# relay_board.net
KiCad netlist of a schematic drawn in EAGLE
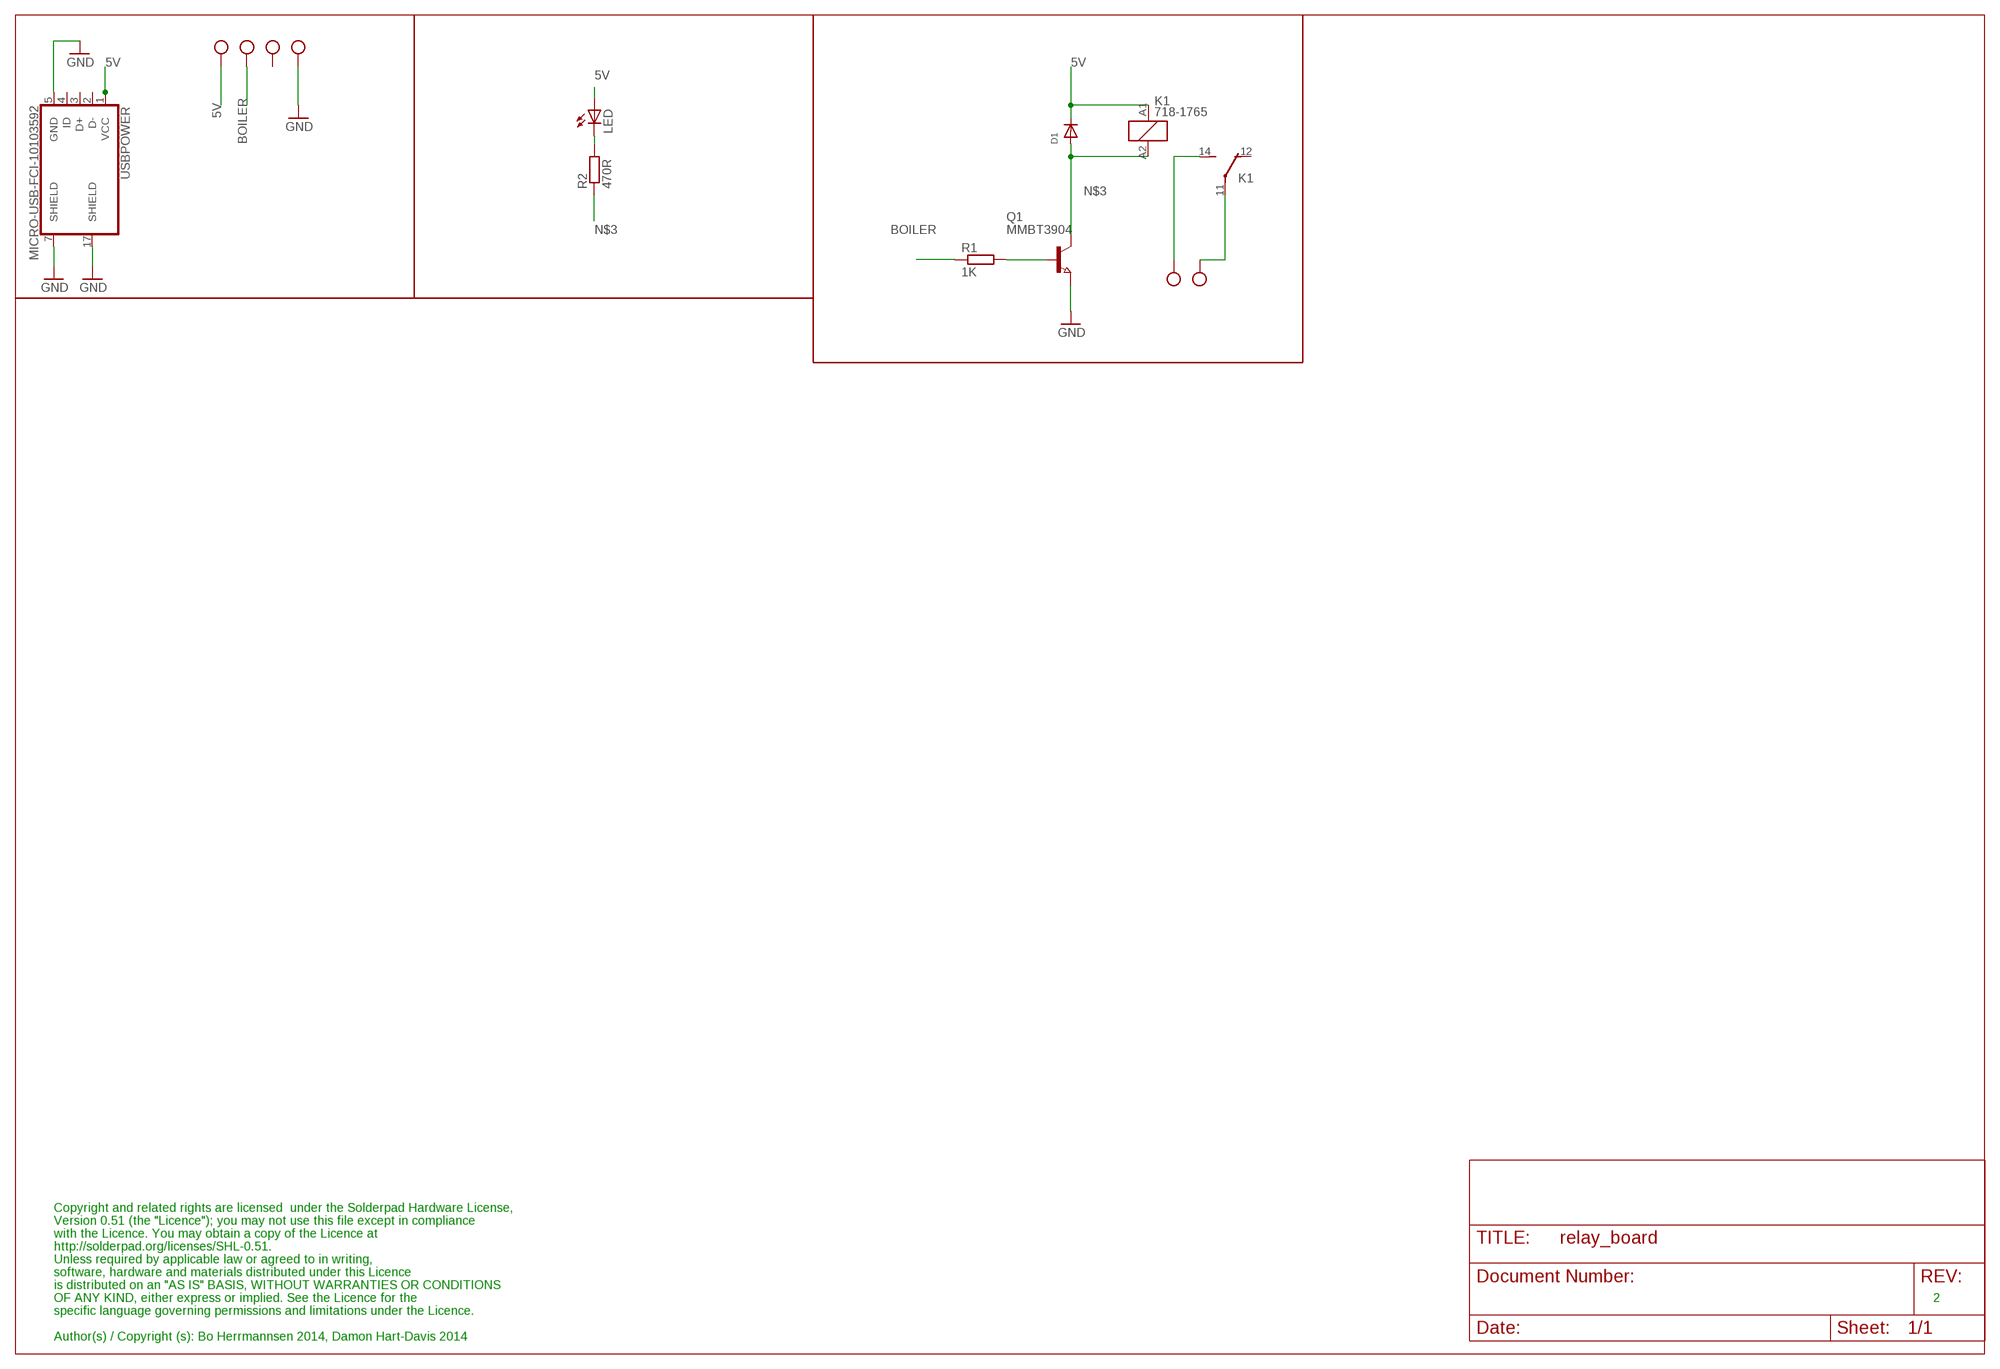
[diagram p0: schematic, sheet 1]

(export (version "E")
  (design (tool "Eeschema 10.0.6"))
  (components
    (comp (ref "D1")
      (value "DIODESMA")
      (footprint "eagle-import:SMADIODE")
      (libsource (lib "eagle-import") (part "DIODESMA"))
    )
    (comp (ref "K1")
      (value "718-1765")
      (footprint "eagle-import:718-1765")
      (libsource (lib "eagle-import") (part "718-1765"))
    )
    (comp (ref "LED")
      (value "LED3MM")
      (footprint "eagle-import:LED3MM")
      (libsource (lib "eagle-import") (part "LED3MM"))
    )
    (comp (ref "Q1")
      (value "MMBT3904")
      (footprint "eagle-import:SOT23")
      (libsource (lib "eagle-import") (part "NPN-TRANSISTOR_SOT23"))
    )
    (comp (ref "R1")
      (value "1K")
      (footprint "eagle-import:R0603")
      (libsource (lib "eagle-import") (part "R-EU_R0603"))
    )
    (comp (ref "R2")
      (value "470R")
      (footprint "eagle-import:R0603")
      (libsource (lib "eagle-import") (part "R-EU_R0603"))
    )
    (comp (ref "USBPOWER")
      (value "MICRO-USB-FCI-10103592")
      (footprint "eagle-import:MICRO-USB-FCI-10103592")
      (libsource (lib "eagle-import") (part "MICRO-USB-FCI-10103592"))
    )
    (comp (ref "X1")
      (value "W237-102")
      (footprint "eagle-import:SCREWTERMINAL")
      (fields (field (name "MPN") "237-102"))
      (libsource (lib "eagle-import") (part "W237-102"))
    )
    (comp (ref "X2")
      (value "W237-102")
      (footprint "eagle-import:SCREWTERMINAL")
      (fields (field (name "MPN") "237-102"))
      (libsource (lib "eagle-import") (part "W237-102"))
    )
    (comp (ref "X3")
      (value "W237-102")
      (footprint "eagle-import:SCREWTERMINAL")
      (fields (field (name "MPN") "237-102"))
      (libsource (lib "eagle-import") (part "W237-102"))
    )
  )
  (nets
    (net (code "1") (name "/5V") (class "Default")
      (node (ref "D1") (pin "C") (pinfunction "C_C") (pintype "passive"))
      (node (ref "K1") (pin "A1") (pinfunction "1_A1") (pintype "passive"))
      (node (ref "LED") (pin "A") (pinfunction "A_A") (pintype "passive"))
      (node (ref "USBPOWER") (pin "1") (pinfunction "VCC_1") (pintype "bidirectional"))
      (node (ref "X1") (pin "2") (pinfunction "KL_2") (pintype "passive"))
    )
    (net (code "2") (name "/BOILER") (class "Default")
      (node (ref "R1") (pin "1") (pinfunction "1_1") (pintype "passive"))
      (node (ref "X1") (pin "1") (pinfunction "KL_1") (pintype "passive"))
    )
    (net (code "3") (name "/N$3") (class "Default")
      (node (ref "D1") (pin "A") (pinfunction "A_A") (pintype "passive"))
      (node (ref "K1") (pin "A2") (pinfunction "2_A2") (pintype "passive"))
      (node (ref "Q1") (pin "3") (pinfunction "C_3") (pintype "passive"))
      (node (ref "R2") (pin "1") (pinfunction "1_1") (pintype "passive"))
    )
    (net (code "4") (name "GND") (class "Default")
      (node (ref "Q1") (pin "2") (pinfunction "E_2") (pintype "passive"))
      (node (ref "USBPOWER") (pin "17") (pinfunction "SHIELD_17") (pintype "bidirectional"))
      (node (ref "USBPOWER") (pin "5") (pinfunction "GND_5") (pintype "bidirectional"))
      (node (ref "USBPOWER") (pin "7") (pinfunction "SHIELD_7") (pintype "bidirectional"))
      (node (ref "X2") (pin "2") (pinfunction "KL_2") (pintype "passive"))
    )
    (net (code "5") (name "Net-(K1B-P)") (class "Default")
      (node (ref "K1") (pin "11") (pinfunction "P_11") (pintype "passive"))
      (node (ref "X3") (pin "2") (pinfunction "KL_2") (pintype "passive"))
    )
    (net (code "6") (name "Net-(K1B-S)") (class "Default")
      (node (ref "K1") (pin "14") (pinfunction "S_14") (pintype "passive"))
      (node (ref "X3") (pin "1") (pinfunction "KL_1") (pintype "passive"))
    )
    (net (code "7") (name "Net-(LED-C)") (class "Default")
      (node (ref "LED") (pin "K") (pinfunction "C_K") (pintype "passive"))
      (node (ref "R2") (pin "2") (pinfunction "2_2") (pintype "passive"))
    )
    (net (code "8") (name "Net-(Q1-B)") (class "Default")
      (node (ref "Q1") (pin "1") (pinfunction "B_1") (pintype "passive"))
      (node (ref "R1") (pin "2") (pinfunction "2_2") (pintype "passive"))
    )
    (net (code "9") (name "unconnected-(K1B-O-Pad12)") (class "Default")
      (node (ref "K1") (pin "12") (pinfunction "O_12") (pintype "passive"))
    )
    (net (code "10") (name "unconnected-(USBPOWER-D+-Pad3)") (class "Default")
      (node (ref "USBPOWER") (pin "3") (pinfunction "D+_3") (pintype "bidirectional"))
    )
    (net (code "11") (name "unconnected-(USBPOWER-D--Pad2)") (class "Default")
      (node (ref "USBPOWER") (pin "2") (pinfunction "D-_2") (pintype "bidirectional"))
    )
    (net (code "12") (name "unconnected-(USBPOWER-ID-Pad4)") (class "Default")
      (node (ref "USBPOWER") (pin "4") (pinfunction "ID_4") (pintype "bidirectional"))
    )
    (net (code "13") (name "unconnected-(X2A-KL-Pad1)") (class "Default")
      (node (ref "X2") (pin "1") (pinfunction "KL_1") (pintype "passive"))
    )
  )
)
